# Interface_-_CAN.net
KiCad netlist of a schematic drawn in Altium Designer
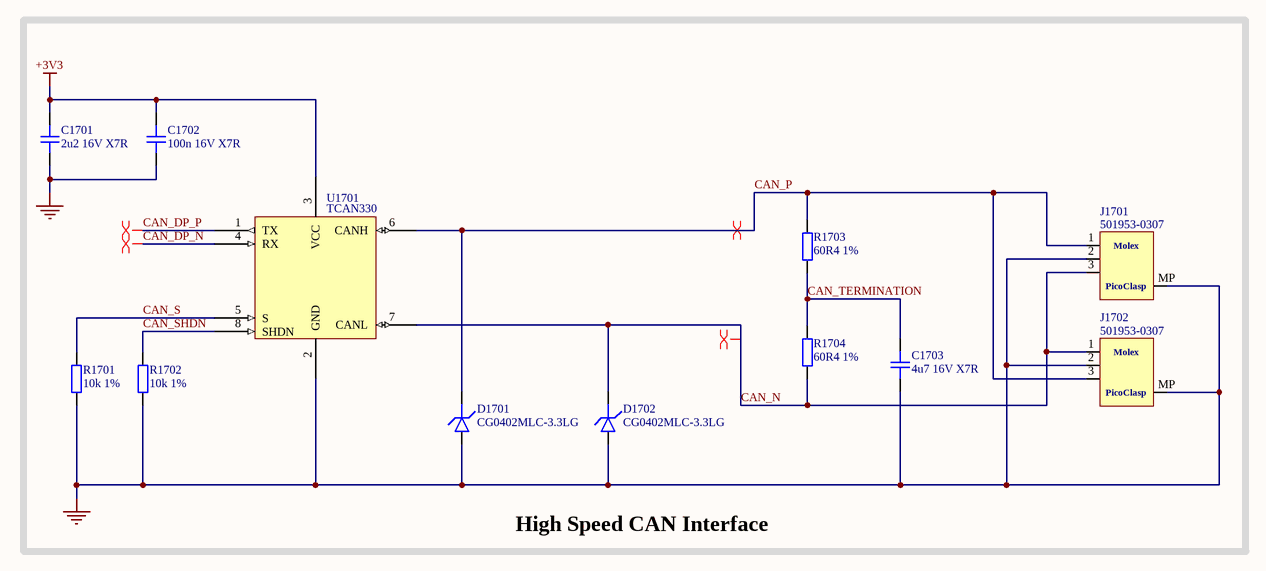
[diagram p0: Interface - CAN.SchDoc]

(export (version "E")
  (design (tool "Eeschema 10.0.6"))
  (components
    (comp (ref "C1701")
      (value "2u2 16V X7R")
      (footprint "CAP_0603")
      (description "Capacitor SMD 0603")
      (fields
        (field (name "MANUFACTURER") "YAGEO")
        (field (name "MANUFACTURER PART NUMBER") "CC0603KRX7R7BB225")
      )
      (libsource (lib "Schematic-Lib-PhilsLab") (part "CAP_0603"))
    )
    (comp (ref "C1702")
      (value "100n 16V X7R")
      (footprint "CAP_0402")
      (description "Capacitor SMD 0402")
      (fields
        (field (name "MANUFACTURER") "YAGEO")
        (field (name "MANUFACTURER PART NUMBER") "CC0402JRX7R7BB104")
      )
      (libsource (lib "Schematic-Lib-PhilsLab") (part "CAP_0402"))
    )
    (comp (ref "C1703")
      (value "4u7 16V X7R")
      (footprint "CAP_0402")
      (description "Capacitor SMD 0402")
      (fields
        (field (name "MANUFACTURER") "Murata Electronics")
        (field (name "MANUFACTURER PART NUMBER") "GRM155D81C475ME15D")
      )
      (libsource (lib "Schematic-Lib-PhilsLab") (part "CAP_0402"))
    )
    (comp (ref "D1701")
      (value "CG0402MLC-3.3LG")
      (footprint "D_0402")
      (description "Diode TVS / ESD 0402")
      (libsource (lib "Schematic-Lib-PhilsLab") (part "D_TVS_0402"))
    )
    (comp (ref "D1702")
      (value "CG0402MLC-3.3LG")
      (footprint "D_0402")
      (description "Diode TVS / ESD 0402")
      (libsource (lib "Schematic-Lib-PhilsLab") (part "D_TVS_0402"))
    )
    (comp (ref "J1701")
      (value "501953-0307")
      (footprint "5019530307")
      (description "Headers & Wire Housings 1.0WtBWaferAssyR/A1- -Row3Ckt+LKEmbsTpPkg")
      (libsource (lib "Schematic-Lib-PhilsLab") (part "501953-0307"))
    )
    (comp (ref "J1702")
      (value "501953-0307")
      (footprint "5019530307")
      (description "Headers & Wire Housings 1.0WtBWaferAssyR/A1- -Row3Ckt+LKEmbsTpPkg")
      (libsource (lib "Schematic-Lib-PhilsLab") (part "501953-0307"))
    )
    (comp (ref "R1701")
      (value "10k 1%")
      (footprint "RES_0402")
      (description "Resistor SMD 0402")
      (fields
        (field (name "MANUFACTURER") "PANASONIC")
        (field (name "MANUFACTURER PART NUMBER") "ERJPA2F1002X")
      )
      (libsource (lib "Schematic-Lib-PhilsLab") (part "RES_0402"))
    )
    (comp (ref "R1702")
      (value "10k 1%")
      (footprint "RES_0402")
      (description "Resistor SMD 0402")
      (fields
        (field (name "MANUFACTURER") "PANASONIC")
        (field (name "MANUFACTURER PART NUMBER") "ERJPA2F1002X")
      )
      (libsource (lib "Schematic-Lib-PhilsLab") (part "RES_0402"))
    )
    (comp (ref "R1703")
      (value "60R4 1%")
      (footprint "RES_0402")
      (description "Resistor SMD 0402")
      (fields
        (field (name "MANUFACTURER") "PANASONIC")
        (field (name "MANUFACTURER PART NUMBER") "ERJ2RKF60R4X")
      )
      (libsource (lib "Schematic-Lib-PhilsLab") (part "RES_0402"))
    )
    (comp (ref "R1704")
      (value "60R4 1%")
      (footprint "RES_0402")
      (description "Resistor SMD 0402")
      (fields
        (field (name "MANUFACTURER") "PANASONIC")
        (field (name "MANUFACTURER PART NUMBER") "ERJ2RKF60R4X")
      )
      (libsource (lib "Schematic-Lib-PhilsLab") (part "RES_0402"))
    )
    (comp (ref "U1701")
      (value "TCAN330")
      (footprint "SOIC-8")
      (description "TCAN33x 3.3-V CAN Transceivers with CAN FD (Flexible Data Rate)")
      (libsource (lib "Schematic-Lib-PhilsLab") (part "TCAN330"))
    )
  )
  (nets
    (net (code "1") (name "+3V3") (class "Default")
      (node (ref "C1701") (pin "2") (pinfunction "2_2") (pintype "passive"))
      (node (ref "C1702") (pin "2") (pinfunction "2_2") (pintype "passive"))
      (node (ref "U1701") (pin "3") (pinfunction "VCC_3") (pintype "power_in"))
    )
    (net (code "2") (name "/CAN_DP_N") (class "Default")
      (node (ref "U1701") (pin "4") (pinfunction "RX_4") (pintype "input"))
    )
    (net (code "3") (name "/CAN_DP_P") (class "Default")
      (node (ref "U1701") (pin "1") (pinfunction "TX_1") (pintype "output"))
    )
    (net (code "4") (name "/CAN_N") (class "Default")
      (node (ref "D1702") (pin "K") (pinfunction "K_K") (pintype "passive"))
      (node (ref "J1701") (pin "3") (pinfunction "3_3") (pintype "passive"))
      (node (ref "J1702") (pin "1") (pinfunction "1_1") (pintype "passive"))
      (node (ref "R1704") (pin "1") (pinfunction "1_1") (pintype "passive"))
      (node (ref "U1701") (pin "7") (pinfunction "CANL_7") (pintype "bidirectional"))
    )
    (net (code "5") (name "/CAN_P") (class "Default")
      (node (ref "D1701") (pin "K") (pinfunction "K_K") (pintype "passive"))
      (node (ref "J1701") (pin "1") (pinfunction "1_1") (pintype "passive"))
      (node (ref "J1702") (pin "3") (pinfunction "3_3") (pintype "passive"))
      (node (ref "R1703") (pin "2") (pinfunction "2_2") (pintype "passive"))
      (node (ref "U1701") (pin "6") (pinfunction "CANH_6") (pintype "bidirectional"))
    )
    (net (code "6") (name "/CAN_S") (class "Default")
      (node (ref "R1701") (pin "2") (pinfunction "2_2") (pintype "passive"))
      (node (ref "U1701") (pin "5") (pinfunction "S_5") (pintype "input"))
    )
    (net (code "7") (name "/CAN_SHDN") (class "Default")
      (node (ref "R1702") (pin "2") (pinfunction "2_2") (pintype "passive"))
      (node (ref "U1701") (pin "8") (pinfunction "SHDN_8") (pintype "input"))
    )
    (net (code "8") (name "/CAN_TERMINATION") (class "Default")
      (node (ref "C1703") (pin "2") (pinfunction "2_2") (pintype "passive"))
      (node (ref "R1703") (pin "1") (pinfunction "1_1") (pintype "passive"))
      (node (ref "R1704") (pin "2") (pinfunction "2_2") (pintype "passive"))
    )
    (net (code "9") (name "GND") (class "Default")
      (node (ref "C1701") (pin "1") (pinfunction "1_1") (pintype "passive"))
      (node (ref "C1702") (pin "1") (pinfunction "1_1") (pintype "passive"))
      (node (ref "C1703") (pin "1") (pinfunction "1_1") (pintype "passive"))
      (node (ref "D1701") (pin "A") (pinfunction "A_A") (pintype "passive"))
      (node (ref "D1702") (pin "A") (pinfunction "A_A") (pintype "passive"))
      (node (ref "J1701") (pin "2") (pinfunction "2_2") (pintype "passive"))
      (node (ref "J1701") (pin "MP") (pinfunction "MP_MP") (pintype "passive"))
      (node (ref "J1702") (pin "2") (pinfunction "2_2") (pintype "passive"))
      (node (ref "J1702") (pin "MP") (pinfunction "MP_MP") (pintype "passive"))
      (node (ref "R1701") (pin "1") (pinfunction "1_1") (pintype "passive"))
      (node (ref "R1702") (pin "1") (pinfunction "1_1") (pintype "passive"))
      (node (ref "U1701") (pin "2") (pinfunction "GND_2") (pintype "passive"))
    )
  )
)
